# 3V3_LDO.net
KiCad netlist of a schematic drawn in Altium Designer
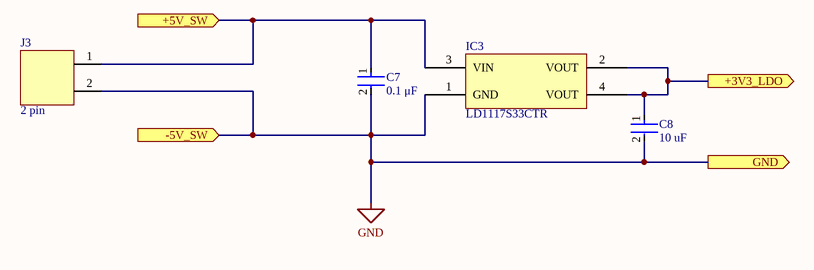
[diagram p0: 3V3 LDO.SchDoc]

(export (version "E")
  (design (tool "Eeschema 10.0.6"))
  (components
    (comp (ref "C7")
      (value "0.1 μF")
      (footprint "FP-C0805C-DN-MFG")
      (description "C0805 0.10 μF X7R 30ppm/°C 20.00% 50 V C0805C104M5RAC")
      (fields
        (field (name "MANUFACTURER PART NUMBER") "C0805C104M5RAC")
        (field (name "MANUFACTURER") "KEMET")
      )
      (libsource (lib "Altium Content Vault") (part "b4654b650e69147ec39a6b967a45e02"))
    )
    (comp (ref "C8")
      (value "10 uF")
      (footprint "FP-C0805C-DG-MFG")
      (description "CAP CER 10UF 10V X5R 0805\r\nC0805C106K8PACTU")
      (fields (field (name "TOLERANCE") "10%") (field (name "MANUFACTURER PART NUMBER") "C0805C106K8PACTU"))
      (libsource (lib "Altium Content Vault") (part "11868f565c42a9108669ba33697ecf6"))
    )
    (comp (ref "IC3")
      (value "LD1117S33CTR")
      (footprint "LD1117")
      (description "IC REG LINEAR 3.3V 800MA SOT223")
      (libsource (lib "Callisto Control Board") (part "LD1117S33CTR"))
    )
    (comp (ref "J3")
      (value "2 pin")
      (footprint "2 pin terminal 5mm")
      (description "2 pin terminal block 5 mm")
      (libsource (lib "Callisto Control Board") (part "2 pin terminal block 5 mm"))
    )
  )
  (nets
    (net (code "1") (name "/+3V3_LDO") (class "Default")
      (node (ref "C8") (pin "1") (pinfunction "1_1") (pintype "passive"))
      (node (ref "IC3") (pin "2") (pinfunction "VOUT_2") (pintype "passive"))
      (node (ref "IC3") (pin "4") (pinfunction "VOUT_4") (pintype "passive"))
    )
    (net (code "2") (name "/+5V_SW") (class "Default")
      (node (ref "C7") (pin "1") (pinfunction "1_1") (pintype "passive"))
      (node (ref "IC3") (pin "3") (pinfunction "VIN_3") (pintype "passive"))
      (node (ref "J3") (pin "1") (pintype "passive"))
    )
    (net (code "3") (name "GND") (class "Default")
      (node (ref "C7") (pin "2") (pinfunction "2_2") (pintype "passive"))
      (node (ref "C8") (pin "2") (pinfunction "2_2") (pintype "passive"))
      (node (ref "IC3") (pin "1") (pinfunction "GND_1") (pintype "passive"))
      (node (ref "J3") (pin "2") (pintype "passive"))
    )
  )
)
